# Sitara_Connectors.net
KiCad netlist of a schematic drawn in Altium Designer
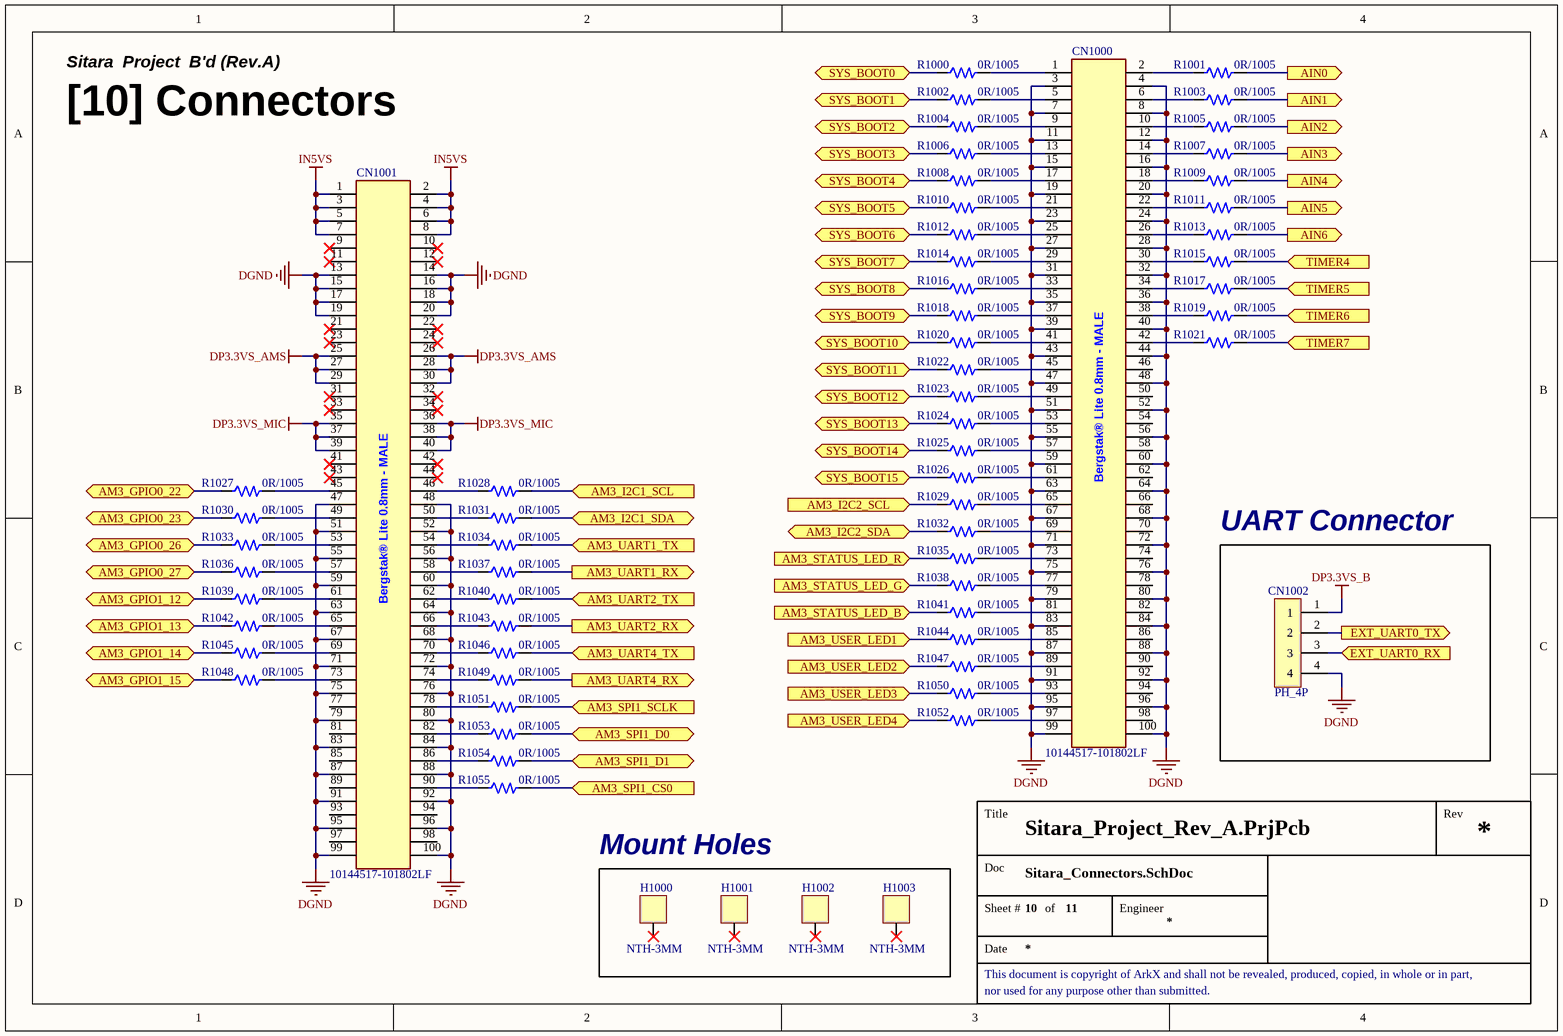
[diagram p0: Sitara_Connectors.SchDoc]

(export (version "E")
  (design (tool "Eeschema 10.0.6"))
  (components
    (comp (ref "CN1000")
      (value "10144517-101802LF")
      (footprint "CON_BergStak-Lite(0.8mm)_MALE-100P(10144517-101802LF)_HandSolder")
      (libsource (lib "Arkx") (part "CON_BergStak-Lite(0.8mm)_MALE-100P(10144517-101802LF)"))
    )
    (comp (ref "CN1001")
      (value "10144517-101802LF")
      (footprint "CON_BergStak-Lite(0.8mm)_MALE-100P(10144517-101802LF)_HandSolder")
      (libsource (lib "Arkx") (part "CON_BergStak-Lite(0.8mm)_MALE-100P(10144517-101802LF)"))
    )
    (comp (ref "CN1002")
      (value "PH_4P")
      (footprint "CON PIN_HEADER-4PIN(2.54MM)")
      (description "CON_PIN_HEADER_SINGLE-4PIN(2.54MM)")
      (libsource (lib "Arkx") (part "CON_PIN_HEADER_SINGLE-4PIN(2.54MM)"))
    )
    (comp (ref "H1000")
      (value "NTH-3MM")
      (footprint "HOLE NTH-3MM")
      (description "Non-Through Hole 3mm")
      (libsource (lib "Arkx") (part "HOLE_NTH-3MM"))
    )
    (comp (ref "H1001")
      (value "NTH-3MM")
      (footprint "HOLE NTH-3MM")
      (description "Non-Through Hole 3mm")
      (libsource (lib "Arkx") (part "HOLE_NTH-3MM"))
    )
    (comp (ref "H1002")
      (value "NTH-3MM")
      (footprint "HOLE NTH-3MM")
      (description "Non-Through Hole 3mm")
      (libsource (lib "Arkx") (part "HOLE_NTH-3MM"))
    )
    (comp (ref "H1003")
      (value "NTH-3MM")
      (footprint "HOLE NTH-3MM")
      (description "Non-Through Hole 3mm")
      (libsource (lib "Arkx") (part "HOLE_NTH-3MM"))
    )
    (comp (ref "R1000")
      (value "0R/1005")
      (footprint "RES 1005 (0402_inch)")
      (description "RES_0R/1005/62.5mW")
      (fields (field (name "LCSC PART #") "C17168"))
      (libsource (lib "Arkx") (part "RES_0R/1005/62.5mW"))
    )
    (comp (ref "R1001")
      (value "0R/1005")
      (footprint "RES 1005 (0402_inch)")
      (description "RES_0R/1005/62.5mW")
      (fields (field (name "LCSC PART #") "C17168"))
      (libsource (lib "Arkx") (part "RES_0R/1005/62.5mW"))
    )
    (comp (ref "R1002")
      (value "0R/1005")
      (footprint "RES 1005 (0402_inch)")
      (description "RES_0R/1005/62.5mW")
      (fields (field (name "LCSC PART #") "C17168"))
      (libsource (lib "Arkx") (part "RES_0R/1005/62.5mW"))
    )
    (comp (ref "R1003")
      (value "0R/1005")
      (footprint "RES 1005 (0402_inch)")
      (description "RES_0R/1005/62.5mW")
      (fields (field (name "LCSC PART #") "C17168"))
      (libsource (lib "Arkx") (part "RES_0R/1005/62.5mW"))
    )
    (comp (ref "R1004")
      (value "0R/1005")
      (footprint "RES 1005 (0402_inch)")
      (description "RES_0R/1005/62.5mW")
      (fields (field (name "LCSC PART #") "C17168"))
      (libsource (lib "Arkx") (part "RES_0R/1005/62.5mW"))
    )
    (comp (ref "R1005")
      (value "0R/1005")
      (footprint "RES 1005 (0402_inch)")
      (description "RES_0R/1005/62.5mW")
      (fields (field (name "LCSC PART #") "C17168"))
      (libsource (lib "Arkx") (part "RES_0R/1005/62.5mW"))
    )
    (comp (ref "R1006")
      (value "0R/1005")
      (footprint "RES 1005 (0402_inch)")
      (description "RES_0R/1005/62.5mW")
      (fields (field (name "LCSC PART #") "C17168"))
      (libsource (lib "Arkx") (part "RES_0R/1005/62.5mW"))
    )
    (comp (ref "R1007")
      (value "0R/1005")
      (footprint "RES 1005 (0402_inch)")
      (description "RES_0R/1005/62.5mW")
      (fields (field (name "LCSC PART #") "C17168"))
      (libsource (lib "Arkx") (part "RES_0R/1005/62.5mW"))
    )
    (comp (ref "R1008")
      (value "0R/1005")
      (footprint "RES 1005 (0402_inch)")
      (description "RES_0R/1005/62.5mW")
      (fields (field (name "LCSC PART #") "C17168"))
      (libsource (lib "Arkx") (part "RES_0R/1005/62.5mW"))
    )
    (comp (ref "R1009")
      (value "0R/1005")
      (footprint "RES 1005 (0402_inch)")
      (description "RES_0R/1005/62.5mW")
      (fields (field (name "LCSC PART #") "C17168"))
      (libsource (lib "Arkx") (part "RES_0R/1005/62.5mW"))
    )
    (comp (ref "R1010")
      (value "0R/1005")
      (footprint "RES 1005 (0402_inch)")
      (description "RES_0R/1005/62.5mW")
      (fields (field (name "LCSC PART #") "C17168"))
      (libsource (lib "Arkx") (part "RES_0R/1005/62.5mW"))
    )
    (comp (ref "R1011")
      (value "0R/1005")
      (footprint "RES 1005 (0402_inch)")
      (description "RES_0R/1005/62.5mW")
      (fields (field (name "LCSC PART #") "C17168"))
      (libsource (lib "Arkx") (part "RES_0R/1005/62.5mW"))
    )
    (comp (ref "R1012")
      (value "0R/1005")
      (footprint "RES 1005 (0402_inch)")
      (description "RES_0R/1005/62.5mW")
      (fields (field (name "LCSC PART #") "C17168"))
      (libsource (lib "Arkx") (part "RES_0R/1005/62.5mW"))
    )
    (comp (ref "R1013")
      (value "0R/1005")
      (footprint "RES 1005 (0402_inch)")
      (description "RES_0R/1005/62.5mW")
      (fields (field (name "LCSC PART #") "C17168"))
      (libsource (lib "Arkx") (part "RES_0R/1005/62.5mW"))
    )
    (comp (ref "R1014")
      (value "0R/1005")
      (footprint "RES 1005 (0402_inch)")
      (description "RES_0R/1005/62.5mW")
      (fields (field (name "LCSC PART #") "C17168"))
      (libsource (lib "Arkx") (part "RES_0R/1005/62.5mW"))
    )
    (comp (ref "R1015")
      (value "0R/1005")
      (footprint "RES 1005 (0402_inch)")
      (description "RES_0R/1005/62.5mW")
      (fields (field (name "LCSC PART #") "C17168"))
      (libsource (lib "Arkx") (part "RES_0R/1005/62.5mW"))
    )
    (comp (ref "R1016")
      (value "0R/1005")
      (footprint "RES 1005 (0402_inch)")
      (description "RES_0R/1005/62.5mW")
      (fields (field (name "LCSC PART #") "C17168"))
      (libsource (lib "Arkx") (part "RES_0R/1005/62.5mW"))
    )
    (comp (ref "R1017")
      (value "0R/1005")
      (footprint "RES 1005 (0402_inch)")
      (description "RES_0R/1005/62.5mW")
      (fields (field (name "LCSC PART #") "C17168"))
      (libsource (lib "Arkx") (part "RES_0R/1005/62.5mW"))
    )
    (comp (ref "R1018")
      (value "0R/1005")
      (footprint "RES 1005 (0402_inch)")
      (description "RES_0R/1005/62.5mW")
      (fields (field (name "LCSC PART #") "C17168"))
      (libsource (lib "Arkx") (part "RES_0R/1005/62.5mW"))
    )
    (comp (ref "R1019")
      (value "0R/1005")
      (footprint "RES 1005 (0402_inch)")
      (description "RES_0R/1005/62.5mW")
      (fields (field (name "LCSC PART #") "C17168"))
      (libsource (lib "Arkx") (part "RES_0R/1005/62.5mW"))
    )
    (comp (ref "R1020")
      (value "0R/1005")
      (footprint "RES 1005 (0402_inch)")
      (description "RES_0R/1005/62.5mW")
      (fields (field (name "LCSC PART #") "C17168"))
      (libsource (lib "Arkx") (part "RES_0R/1005/62.5mW"))
    )
    (comp (ref "R1021")
      (value "0R/1005")
      (footprint "RES 1005 (0402_inch)")
      (description "RES_0R/1005/62.5mW")
      (fields (field (name "LCSC PART #") "C17168"))
      (libsource (lib "Arkx") (part "RES_0R/1005/62.5mW"))
    )
    (comp (ref "R1022")
      (value "0R/1005")
      (footprint "RES 1005 (0402_inch)")
      (description "RES_0R/1005/62.5mW")
      (fields (field (name "LCSC PART #") "C17168"))
      (libsource (lib "Arkx") (part "RES_0R/1005/62.5mW"))
    )
    (comp (ref "R1023")
      (value "0R/1005")
      (footprint "RES 1005 (0402_inch)")
      (description "RES_0R/1005/62.5mW")
      (fields (field (name "LCSC PART #") "C17168"))
      (libsource (lib "Arkx") (part "RES_0R/1005/62.5mW"))
    )
    (comp (ref "R1024")
      (value "0R/1005")
      (footprint "RES 1005 (0402_inch)")
      (description "RES_0R/1005/62.5mW")
      (fields (field (name "LCSC PART #") "C17168"))
      (libsource (lib "Arkx") (part "RES_0R/1005/62.5mW"))
    )
    (comp (ref "R1025")
      (value "0R/1005")
      (footprint "RES 1005 (0402_inch)")
      (description "RES_0R/1005/62.5mW")
      (fields (field (name "LCSC PART #") "C17168"))
      (libsource (lib "Arkx") (part "RES_0R/1005/62.5mW"))
    )
    (comp (ref "R1026")
      (value "0R/1005")
      (footprint "RES 1005 (0402_inch)")
      (description "RES_0R/1005/62.5mW")
      (fields (field (name "LCSC PART #") "C17168"))
      (libsource (lib "Arkx") (part "RES_0R/1005/62.5mW"))
    )
    (comp (ref "R1027")
      (value "0R/1005")
      (footprint "RES 1005 (0402_inch)")
      (description "RES_0R/1005/62.5mW")
      (fields (field (name "LCSC PART #") "C17168"))
      (libsource (lib "Arkx") (part "RES_0R/1005/62.5mW"))
    )
    (comp (ref "R1028")
      (value "0R/1005")
      (footprint "RES 1005 (0402_inch)")
      (description "RES_0R/1005/62.5mW")
      (fields (field (name "LCSC PART #") "C17168"))
      (libsource (lib "Arkx") (part "RES_0R/1005/62.5mW"))
    )
    (comp (ref "R1029")
      (value "0R/1005")
      (footprint "RES 1005 (0402_inch)")
      (description "RES_0R/1005/62.5mW")
      (fields (field (name "LCSC PART #") "C17168"))
      (libsource (lib "Arkx") (part "RES_0R/1005/62.5mW"))
    )
    (comp (ref "R1030")
      (value "0R/1005")
      (footprint "RES 1005 (0402_inch)")
      (description "RES_0R/1005/62.5mW")
      (fields (field (name "LCSC PART #") "C17168"))
      (libsource (lib "Arkx") (part "RES_0R/1005/62.5mW"))
    )
    (comp (ref "R1031")
      (value "0R/1005")
      (footprint "RES 1005 (0402_inch)")
      (description "RES_0R/1005/62.5mW")
      (fields (field (name "LCSC PART #") "C17168"))
      (libsource (lib "Arkx") (part "RES_0R/1005/62.5mW"))
    )
    (comp (ref "R1032")
      (value "0R/1005")
      (footprint "RES 1005 (0402_inch)")
      (description "RES_0R/1005/62.5mW")
      (fields (field (name "LCSC PART #") "C17168"))
      (libsource (lib "Arkx") (part "RES_0R/1005/62.5mW"))
    )
    (comp (ref "R1033")
      (value "0R/1005")
      (footprint "RES 1005 (0402_inch)")
      (description "RES_0R/1005/62.5mW")
      (fields (field (name "LCSC PART #") "C17168"))
      (libsource (lib "Arkx") (part "RES_0R/1005/62.5mW"))
    )
    (comp (ref "R1034")
      (value "0R/1005")
      (footprint "RES 1005 (0402_inch)")
      (description "RES_0R/1005/62.5mW")
      (fields (field (name "LCSC PART #") "C17168"))
      (libsource (lib "Arkx") (part "RES_0R/1005/62.5mW"))
    )
    (comp (ref "R1035")
      (value "0R/1005")
      (footprint "RES 1005 (0402_inch)")
      (description "RES_0R/1005/62.5mW")
      (fields (field (name "LCSC PART #") "C17168"))
      (libsource (lib "Arkx") (part "RES_0R/1005/62.5mW"))
    )
    (comp (ref "R1036")
      (value "0R/1005")
      (footprint "RES 1005 (0402_inch)")
      (description "RES_0R/1005/62.5mW")
      (fields (field (name "LCSC PART #") "C17168"))
      (libsource (lib "Arkx") (part "RES_0R/1005/62.5mW"))
    )
    (comp (ref "R1037")
      (value "0R/1005")
      (footprint "RES 1005 (0402_inch)")
      (description "RES_0R/1005/62.5mW")
      (fields (field (name "LCSC PART #") "C17168"))
      (libsource (lib "Arkx") (part "RES_0R/1005/62.5mW"))
    )
    (comp (ref "R1038")
      (value "0R/1005")
      (footprint "RES 1005 (0402_inch)")
      (description "RES_0R/1005/62.5mW")
      (fields (field (name "LCSC PART #") "C17168"))
      (libsource (lib "Arkx") (part "RES_0R/1005/62.5mW"))
    )
    (comp (ref "R1039")
      (value "0R/1005")
      (footprint "RES 1005 (0402_inch)")
      (description "RES_0R/1005/62.5mW")
      (fields (field (name "LCSC PART #") "C17168"))
      (libsource (lib "Arkx") (part "RES_0R/1005/62.5mW"))
    )
    (comp (ref "R1040")
      (value "0R/1005")
      (footprint "RES 1005 (0402_inch)")
      (description "RES_0R/1005/62.5mW")
      (fields (field (name "LCSC PART #") "C17168"))
      (libsource (lib "Arkx") (part "RES_0R/1005/62.5mW"))
    )
    (comp (ref "R1041")
      (value "0R/1005")
      (footprint "RES 1005 (0402_inch)")
      (description "RES_0R/1005/62.5mW")
      (fields (field (name "LCSC PART #") "C17168"))
      (libsource (lib "Arkx") (part "RES_0R/1005/62.5mW"))
    )
    (comp (ref "R1042")
      (value "0R/1005")
      (footprint "RES 1005 (0402_inch)")
      (description "RES_0R/1005/62.5mW")
      (fields (field (name "LCSC PART #") "C17168"))
      (libsource (lib "Arkx") (part "RES_0R/1005/62.5mW"))
    )
    (comp (ref "R1043")
      (value "0R/1005")
      (footprint "RES 1005 (0402_inch)")
      (description "RES_0R/1005/62.5mW")
      (fields (field (name "LCSC PART #") "C17168"))
      (libsource (lib "Arkx") (part "RES_0R/1005/62.5mW"))
    )
    (comp (ref "R1044")
      (value "0R/1005")
      (footprint "RES 1005 (0402_inch)")
      (description "RES_0R/1005/62.5mW")
      (fields (field (name "LCSC PART #") "C17168"))
      (libsource (lib "Arkx") (part "RES_0R/1005/62.5mW"))
    )
    (comp (ref "R1045")
      (value "0R/1005")
      (footprint "RES 1005 (0402_inch)")
      (description "RES_0R/1005/62.5mW")
      (fields (field (name "LCSC PART #") "C17168"))
      (libsource (lib "Arkx") (part "RES_0R/1005/62.5mW"))
    )
    (comp (ref "R1046")
      (value "0R/1005")
      (footprint "RES 1005 (0402_inch)")
      (description "RES_0R/1005/62.5mW")
      (fields (field (name "LCSC PART #") "C17168"))
      (libsource (lib "Arkx") (part "RES_0R/1005/62.5mW"))
    )
    (comp (ref "R1047")
      (value "0R/1005")
      (footprint "RES 1005 (0402_inch)")
      (description "RES_0R/1005/62.5mW")
      (fields (field (name "LCSC PART #") "C17168"))
      (libsource (lib "Arkx") (part "RES_0R/1005/62.5mW"))
    )
    (comp (ref "R1048")
      (value "0R/1005")
      (footprint "RES 1005 (0402_inch)")
      (description "RES_0R/1005/62.5mW")
      (fields (field (name "LCSC PART #") "C17168"))
      (libsource (lib "Arkx") (part "RES_0R/1005/62.5mW"))
    )
    (comp (ref "R1049")
      (value "0R/1005")
      (footprint "RES 1005 (0402_inch)")
      (description "RES_0R/1005/62.5mW")
      (fields (field (name "LCSC PART #") "C17168"))
      (libsource (lib "Arkx") (part "RES_0R/1005/62.5mW"))
    )
    (comp (ref "R1050")
      (value "0R/1005")
      (footprint "RES 1005 (0402_inch)")
      (description "RES_0R/1005/62.5mW")
      (fields (field (name "LCSC PART #") "C17168"))
      (libsource (lib "Arkx") (part "RES_0R/1005/62.5mW"))
    )
    (comp (ref "R1051")
      (value "0R/1005")
      (footprint "RES 1005 (0402_inch)")
      (description "RES_0R/1005/62.5mW")
      (fields (field (name "LCSC PART #") "C17168"))
      (libsource (lib "Arkx") (part "RES_0R/1005/62.5mW"))
    )
    (comp (ref "R1052")
      (value "0R/1005")
      (footprint "RES 1005 (0402_inch)")
      (description "RES_0R/1005/62.5mW")
      (fields (field (name "LCSC PART #") "C17168"))
      (libsource (lib "Arkx") (part "RES_0R/1005/62.5mW"))
    )
    (comp (ref "R1053")
      (value "0R/1005")
      (footprint "RES 1005 (0402_inch)")
      (description "RES_0R/1005/62.5mW")
      (fields (field (name "LCSC PART #") "C17168"))
      (libsource (lib "Arkx") (part "RES_0R/1005/62.5mW"))
    )
    (comp (ref "R1054")
      (value "0R/1005")
      (footprint "RES 1005 (0402_inch)")
      (description "RES_0R/1005/62.5mW")
      (fields (field (name "LCSC PART #") "C17168"))
      (libsource (lib "Arkx") (part "RES_0R/1005/62.5mW"))
    )
    (comp (ref "R1055")
      (value "0R/1005")
      (footprint "RES 1005 (0402_inch)")
      (description "RES_0R/1005/62.5mW")
      (fields (field (name "LCSC PART #") "C17168"))
      (libsource (lib "Arkx") (part "RES_0R/1005/62.5mW"))
    )
  )
  (nets
    (net (code "1") (name "/AIN0") (class "Default")
      (node (ref "R1001") (pin "2") (pinfunction "2_2") (pintype "passive"))
    )
    (net (code "2") (name "/AIN1") (class "Default")
      (node (ref "R1003") (pin "2") (pinfunction "2_2") (pintype "passive"))
    )
    (net (code "3") (name "/AIN2") (class "Default")
      (node (ref "R1005") (pin "2") (pinfunction "2_2") (pintype "passive"))
    )
    (net (code "4") (name "/AIN3") (class "Default")
      (node (ref "R1007") (pin "2") (pinfunction "2_2") (pintype "passive"))
    )
    (net (code "5") (name "/AIN4") (class "Default")
      (node (ref "R1009") (pin "2") (pinfunction "2_2") (pintype "passive"))
    )
    (net (code "6") (name "/AIN5") (class "Default")
      (node (ref "R1011") (pin "2") (pinfunction "2_2") (pintype "passive"))
    )
    (net (code "7") (name "/AIN6") (class "Default")
      (node (ref "R1013") (pin "2") (pinfunction "2_2") (pintype "passive"))
    )
    (net (code "8") (name "/AM3_GPIO0_22") (class "Default")
      (node (ref "R1027") (pin "1") (pinfunction "1_1") (pintype "passive"))
    )
    (net (code "9") (name "/AM3_GPIO0_23") (class "Default")
      (node (ref "R1030") (pin "1") (pinfunction "1_1") (pintype "passive"))
    )
    (net (code "10") (name "/AM3_GPIO0_26") (class "Default")
      (node (ref "R1033") (pin "1") (pinfunction "1_1") (pintype "passive"))
    )
    (net (code "11") (name "/AM3_GPIO0_27") (class "Default")
      (node (ref "R1036") (pin "1") (pinfunction "1_1") (pintype "passive"))
    )
    (net (code "12") (name "/AM3_GPIO1_12") (class "Default")
      (node (ref "R1039") (pin "1") (pinfunction "1_1") (pintype "passive"))
    )
    (net (code "13") (name "/AM3_GPIO1_13") (class "Default")
      (node (ref "R1042") (pin "1") (pinfunction "1_1") (pintype "passive"))
    )
    (net (code "14") (name "/AM3_GPIO1_14") (class "Default")
      (node (ref "R1045") (pin "1") (pinfunction "1_1") (pintype "passive"))
    )
    (net (code "15") (name "/AM3_GPIO1_15") (class "Default")
      (node (ref "R1048") (pin "1") (pinfunction "1_1") (pintype "passive"))
    )
    (net (code "16") (name "/AM3_I2C1_SCL") (class "Default")
      (node (ref "R1028") (pin "2") (pinfunction "2_2") (pintype "passive"))
    )
    (net (code "17") (name "/AM3_I2C1_SDA") (class "Default")
      (node (ref "R1031") (pin "2") (pinfunction "2_2") (pintype "passive"))
    )
    (net (code "18") (name "/AM3_I2C2_SCL") (class "Default")
      (node (ref "R1029") (pin "1") (pinfunction "1_1") (pintype "passive"))
    )
    (net (code "19") (name "/AM3_I2C2_SDA") (class "Default")
      (node (ref "R1032") (pin "1") (pinfunction "1_1") (pintype "passive"))
    )
    (net (code "20") (name "/AM3_SPI1_CS0") (class "Default")
      (node (ref "R1055") (pin "2") (pinfunction "2_2") (pintype "passive"))
    )
    (net (code "21") (name "/AM3_SPI1_D0") (class "Default")
      (node (ref "R1053") (pin "2") (pinfunction "2_2") (pintype "passive"))
    )
    (net (code "22") (name "/AM3_SPI1_D1") (class "Default")
      (node (ref "R1054") (pin "2") (pinfunction "2_2") (pintype "passive"))
    )
    (net (code "23") (name "/AM3_SPI1_SCLK") (class "Default")
      (node (ref "R1051") (pin "2") (pinfunction "2_2") (pintype "passive"))
    )
    (net (code "24") (name "/AM3_STATUS_LED_B") (class "Default")
      (node (ref "R1041") (pin "1") (pinfunction "1_1") (pintype "passive"))
    )
    (net (code "25") (name "/AM3_STATUS_LED_G") (class "Default")
      (node (ref "R1038") (pin "1") (pinfunction "1_1") (pintype "passive"))
    )
    (net (code "26") (name "/AM3_STATUS_LED_R") (class "Default")
      (node (ref "R1035") (pin "1") (pinfunction "1_1") (pintype "passive"))
    )
    (net (code "27") (name "/AM3_UART1_RX") (class "Default")
      (node (ref "R1037") (pin "2") (pinfunction "2_2") (pintype "passive"))
    )
    (net (code "28") (name "/AM3_UART1_TX") (class "Default")
      (node (ref "R1034") (pin "2") (pinfunction "2_2") (pintype "passive"))
    )
    (net (code "29") (name "/AM3_UART2_RX") (class "Default")
      (node (ref "R1043") (pin "2") (pinfunction "2_2") (pintype "passive"))
    )
    (net (code "30") (name "/AM3_UART2_TX") (class "Default")
      (node (ref "R1040") (pin "2") (pinfunction "2_2") (pintype "passive"))
    )
    (net (code "31") (name "/AM3_UART4_RX") (class "Default")
      (node (ref "R1049") (pin "2") (pinfunction "2_2") (pintype "passive"))
    )
    (net (code "32") (name "/AM3_UART4_TX") (class "Default")
      (node (ref "R1046") (pin "2") (pinfunction "2_2") (pintype "passive"))
    )
    (net (code "33") (name "/AM3_USER_LED1") (class "Default")
      (node (ref "R1044") (pin "1") (pinfunction "1_1") (pintype "passive"))
    )
    (net (code "34") (name "/AM3_USER_LED2") (class "Default")
      (node (ref "R1047") (pin "1") (pinfunction "1_1") (pintype "passive"))
    )
    (net (code "35") (name "/AM3_USER_LED3") (class "Default")
      (node (ref "R1050") (pin "1") (pinfunction "1_1") (pintype "passive"))
    )
    (net (code "36") (name "/AM3_USER_LED4") (class "Default")
      (node (ref "R1052") (pin "1") (pinfunction "1_1") (pintype "passive"))
    )
    (net (code "37") (name "/EXT_UART0_RX") (class "Default")
      (node (ref "CN1002") (pin "3") (pinfunction "3_3") (pintype "passive"))
    )
    (net (code "38") (name "/EXT_UART0_TX") (class "Default")
      (node (ref "CN1002") (pin "2") (pinfunction "2_2") (pintype "passive"))
    )
    (net (code "39") (name "/SYS_BOOT0") (class "Default")
      (node (ref "R1000") (pin "1") (pinfunction "1_1") (pintype "passive"))
    )
    (net (code "40") (name "/SYS_BOOT1") (class "Default")
      (node (ref "R1002") (pin "1") (pinfunction "1_1") (pintype "passive"))
    )
    (net (code "41") (name "/SYS_BOOT2") (class "Default")
      (node (ref "R1004") (pin "1") (pinfunction "1_1") (pintype "passive"))
    )
    (net (code "42") (name "/SYS_BOOT3") (class "Default")
      (node (ref "R1006") (pin "1") (pinfunction "1_1") (pintype "passive"))
    )
    (net (code "43") (name "/SYS_BOOT4") (class "Default")
      (node (ref "R1008") (pin "1") (pinfunction "1_1") (pintype "passive"))
    )
    (net (code "44") (name "/SYS_BOOT5") (class "Default")
      (node (ref "R1010") (pin "1") (pinfunction "1_1") (pintype "passive"))
    )
    (net (code "45") (name "/SYS_BOOT6") (class "Default")
      (node (ref "R1012") (pin "1") (pinfunction "1_1") (pintype "passive"))
    )
    (net (code "46") (name "/SYS_BOOT7") (class "Default")
      (node (ref "R1014") (pin "1") (pinfunction "1_1") (pintype "passive"))
    )
    (net (code "47") (name "/SYS_BOOT8") (class "Default")
      (node (ref "R1016") (pin "1") (pinfunction "1_1") (pintype "passive"))
    )
    (net (code "48") (name "/SYS_BOOT9") (class "Default")
      (node (ref "R1018") (pin "1") (pinfunction "1_1") (pintype "passive"))
    )
    (net (code "49") (name "/SYS_BOOT10") (class "Default")
      (node (ref "R1020") (pin "1") (pinfunction "1_1") (pintype "passive"))
    )
    (net (code "50") (name "/SYS_BOOT11") (class "Default")
      (node (ref "R1022") (pin "1") (pinfunction "1_1") (pintype "passive"))
    )
    (net (code "51") (name "/SYS_BOOT12") (class "Default")
      (node (ref "R1023") (pin "1") (pinfunction "1_1") (pintype "passive"))
    )
    (net (code "52") (name "/SYS_BOOT13") (class "Default")
      (node (ref "R1024") (pin "1") (pinfunction "1_1") (pintype "passive"))
    )
    (net (code "53") (name "/SYS_BOOT14") (class "Default")
      (node (ref "R1025") (pin "1") (pinfunction "1_1") (pintype "passive"))
    )
    (net (code "54") (name "/SYS_BOOT15") (class "Default")
      (node (ref "R1026") (pin "1") (pinfunction "1_1") (pintype "passive"))
    )
    (net (code "55") (name "/TIMER4") (class "Default")
      (node (ref "R1015") (pin "2") (pinfunction "2_2") (pintype "passive"))
    )
    (net (code "56") (name "/TIMER5") (class "Default")
      (node (ref "R1017") (pin "2") (pinfunction "2_2") (pintype "passive"))
    )
    (net (code "57") (name "/TIMER6") (class "Default")
      (node (ref "R1019") (pin "2") (pinfunction "2_2") (pintype "passive"))
    )
    (net (code "58") (name "/TIMER7") (class "Default")
      (node (ref "R1021") (pin "2") (pinfunction "2_2") (pintype "passive"))
    )
    (net (code "59") (name "DGND") (class "Default")
      (node (ref "CN1000") (pin "100") (pinfunction "100_100") (pintype "passive"))
      (node (ref "CN1000") (pin "11") (pinfunction "11_11") (pintype "passive"))
      (node (ref "CN1000") (pin "12") (pinfunction "12_12") (pintype "passive"))
      (node (ref "CN1000") (pin "15") (pinfunction "15_15") (pintype "passive"))
      (node (ref "CN1000") (pin "16") (pinfunction "16_16") (pintype "passive"))
      (node (ref "CN1000") (pin "19") (pinfunction "19_19") (pintype "passive"))
      (node (ref "CN1000") (pin "20") (pinfunction "20_20") (pintype "passive"))
      (node (ref "CN1000") (pin "23") (pinfunction "23_23") (pintype "passive"))
      (node (ref "CN1000") (pin "24") (pinfunction "24_24") (pintype "passive"))
      (node (ref "CN1000") (pin "27") (pinfunction "27_27") (pintype "passive"))
      (node (ref "CN1000") (pin "28") (pinfunction "28_28") (pintype "passive"))
      (node (ref "CN1000") (pin "3") (pinfunction "3_3") (pintype "passive"))
      (node (ref "CN1000") (pin "31") (pinfunction "31_31") (pintype "passive"))
      (node (ref "CN1000") (pin "32") (pinfunction "32_32") (pintype "passive"))
      (node (ref "CN1000") (pin "35") (pinfunction "35_35") (pintype "passive"))
      (node (ref "CN1000") (pin "36") (pinfunction "36_36") (pintype "passive"))
      (node (ref "CN1000") (pin "39") (pinfunction "39_39") (pintype "passive"))
      (node (ref "CN1000") (pin "4") (pinfunction "4_4") (pintype "passive"))
      (node (ref "CN1000") (pin "40") (pinfunction "40_40") (pintype "passive"))
      (node (ref "CN1000") (pin "43") (pinfunction "43_43") (pintype "passive"))
      (node (ref "CN1000") (pin "44") (pinfunction "44_44") (pintype "passive"))
      (node (ref "CN1000") (pin "47") (pinfunction "47_47") (pintype "passive"))
      (node (ref "CN1000") (pin "48") (pinfunction "48_48") (pintype "passive"))
      (node (ref "CN1000") (pin "51") (pinfunction "51_51") (pintype "passive"))
      (node (ref "CN1000") (pin "52") (pinfunction "52_52") (pintype "passive"))
      (node (ref "CN1000") (pin "55") (pinfunction "55_55") (pintype "passive"))
      (node (ref "CN1000") (pin "56") (pinfunction "56_56") (pintype "passive"))
      (node (ref "CN1000") (pin "59") (pinfunction "59_59") (pintype "passive"))
      (node (ref "CN1000") (pin "60") (pinfunction "60_60") (pintype "passive"))
      (node (ref "CN1000") (pin "63") (pinfunction "63_63") (pintype "passive"))
      (node (ref "CN1000") (pin "64") (pinfunction "64_64") (pintype "passive"))
      (node (ref "CN1000") (pin "67") (pinfunction "67_67") (pintype "passive"))
      (node (ref "CN1000") (pin "68") (pinfunction "68_68") (pintype "passive"))
      (node (ref "CN1000") (pin "7") (pinfunction "7_7") (pintype "passive"))
      (node (ref "CN1000") (pin "71") (pinfunction "71_71") (pintype "passive"))
      (node (ref "CN1000") (pin "72") (pinfunction "72_72") (pintype "passive"))
      (node (ref "CN1000") (pin "75") (pinfunction "75_75") (pintype "passive"))
      (node (ref "CN1000") (pin "76") (pinfunction "76_76") (pintype "passive"))
      (node (ref "CN1000") (pin "79") (pinfunction "79_79") (pintype "passive"))
      (node (ref "CN1000") (pin "8") (pinfunction "8_8") (pintype "passive"))
      (node (ref "CN1000") (pin "80") (pinfunction "80_80") (pintype "passive"))
      (node (ref "CN1000") (pin "83") (pinfunction "83_83") (pintype "passive"))
      (node (ref "CN1000") (pin "84") (pinfunction "84_84") (pintype "passive"))
      (node (ref "CN1000") (pin "87") (pinfunction "87_87") (pintype "passive"))
      (node (ref "CN1000") (pin "88") (pinfunction "88_88") (pintype "passive"))
      (node (ref "CN1000") (pin "91") (pinfunction "91_91") (pintype "passive"))
      (node (ref "CN1000") (pin "92") (pinfunction "92_92") (pintype "passive"))
      (node (ref "CN1000") (pin "95") (pinfunction "95_95") (pintype "passive"))
      (node (ref "CN1000") (pin "96") (pinfunction "96_96") (pintype "passive"))
      (node (ref "CN1000") (pin "99") (pinfunction "99_99") (pintype "passive"))
      (node (ref "CN1001") (pin "100") (pinfunction "100_100") (pintype "passive"))
      (node (ref "CN1001") (pin "13") (pinfunction "13_13") (pintype "passive"))
      (node (ref "CN1001") (pin "14") (pinfunction "14_14") (pintype "passive"))
      (node (ref "CN1001") (pin "15") (pinfunction "15_15") (pintype "passive"))
      (node (ref "CN1001") (pin "16") (pinfunction "16_16") (pintype "passive"))
      (node (ref "CN1001") (pin "17") (pinfunction "17_17") (pintype "passive"))
      (node (ref "CN1001") (pin "18") (pinfunction "18_18") (pintype "passive"))
      (node (ref "CN1001") (pin "19") (pinfunction "19_19") (pintype "passive"))
      (node (ref "CN1001") (pin "20") (pinfunction "20_20") (pintype "passive"))
      (node (ref "CN1001") (pin "47") (pinfunction "47_47") (pintype "passive"))
      (node (ref "CN1001") (pin "48") (pinfunction "48_48") (pintype "passive"))
      (node (ref "CN1001") (pin "51") (pinfunction "51_51") (pintype "passive"))
      (node (ref "CN1001") (pin "52") (pinfunction "52_52") (pintype "passive"))
      (node (ref "CN1001") (pin "55") (pinfunction "55_55") (pintype "passive"))
      (node (ref "CN1001") (pin "56") (pinfunction "56_56") (pintype "passive"))
      (node (ref "CN1001") (pin "59") (pinfunction "59_59") (pintype "passive"))
      (node (ref "CN1001") (pin "60") (pinfunction "60_60") (pintype "passive"))
      (node (ref "CN1001") (pin "63") (pinfunction "63_63") (pintype "passive"))
      (node (ref "CN1001") (pin "64") (pinfunction "64_64") (pintype "passive"))
      (node (ref "CN1001") (pin "67") (pinfunction "67_67") (pintype "passive"))
      (node (ref "CN1001") (pin "68") (pinfunction "68_68") (pintype "passive"))
      (node (ref "CN1001") (pin "71") (pinfunction "71_71") (pintype "passive"))
      (node (ref "CN1001") (pin "72") (pinfunction "72_72") (pintype "passive"))
      (node (ref "CN1001") (pin "75") (pinfunction "75_75") (pintype "passive"))
      (node (ref "CN1001") (pin "76") (pinfunction "76_76") (pintype "passive"))
      (node (ref "CN1001") (pin "79") (pinfunction "79_79") (pintype "passive"))
      (node (ref "CN1001") (pin "80") (pinfunction "80_80") (pintype "passive"))
      (node (ref "CN1001") (pin "83") (pinfunction "83_83") (pintype "passive"))
      (node (ref "CN1001") (pin "84") (pinfunction "84_84") (pintype "passive"))
      (node (ref "CN1001") (pin "87") (pinfunction "87_87") (pintype "passive"))
      (node (ref "CN1001") (pin "88") (pinfunction "88_88") (pintype "passive"))
      (node (ref "CN1001") (pin "91") (pinfunction "91_91") (pintype "passive"))
      (node (ref "CN1001") (pin "92") (pinfunction "92_92") (pintype "passive"))
      (node (ref "CN1001") (pin "95") (pinfunction "95_95") (pintype "passive"))
      (node (ref "CN1001") (pin "96") (pinfunction "96_96") (pintype "passive"))
      (node (ref "CN1001") (pin "99") (pinfunction "99_99") (pintype "passive"))
      (node (ref "CN1002") (pin "4") (pinfunction "4_4") (pintype "passive"))
    )
    (net (code "60") (name "DP3.3VS_AMS") (class "Default")
      (node (ref "CN1001") (pin "25") (pinfunction "25_25") (pintype "passive"))
      (node (ref "CN1001") (pin "26") (pinfunction "26_26") (pintype "passive"))
      (node (ref "CN1001") (pin "27") (pinfunction "27_27") (pintype "passive"))
      (node (ref "CN1001") (pin "28") (pinfunction "28_28") (pintype "passive"))
      (node (ref "CN1001") (pin "29") (pinfunction "29_29") (pintype "passive"))
      (node (ref "CN1001") (pin "30") (pinfunction "30_30") (pintype "passive"))
    )
    (net (code "61") (name "DP3.3VS_B") (class "Default")
      (node (ref "CN1002") (pin "1") (pinfunction "1_1") (pintype "passive"))
    )
    (net (code "62") (name "DP3.3VS_MIC") (class "Default")
      (node (ref "CN1001") (pin "35") (pinfunction "35_35") (pintype "passive"))
      (node (ref "CN1001") (pin "36") (pinfunction "36_36") (pintype "passive"))
      (node (ref "CN1001") (pin "37") (pinfunction "37_37") (pintype "passive"))
      (node (ref "CN1001") (pin "38") (pinfunction "38_38") (pintype "passive"))
      (node (ref "CN1001") (pin "39") (pinfunction "39_39") (pintype "passive"))
      (node (ref "CN1001") (pin "40") (pinfunction "40_40") (pintype "passive"))
    )
    (net (code "63") (name "IN5VS") (class "Default")
      (node (ref "CN1001") (pin "1") (pinfunction "1_1") (pintype "passive"))
      (node (ref "CN1001") (pin "2") (pinfunction "2_2") (pintype "passive"))
      (node (ref "CN1001") (pin "3") (pinfunction "3_3") (pintype "passive"))
      (node (ref "CN1001") (pin "4") (pinfunction "4_4") (pintype "passive"))
      (node (ref "CN1001") (pin "5") (pinfunction "5_5") (pintype "passive"))
      (node (ref "CN1001") (pin "6") (pinfunction "6_6") (pintype "passive"))
      (node (ref "CN1001") (pin "7") (pinfunction "7_7") (pintype "passive"))
      (node (ref "CN1001") (pin "8") (pinfunction "8_8") (pintype "passive"))
    )
    (net (code "64") (name "Net-(CN1000-Pad1)") (class "Default")
      (node (ref "CN1000") (pin "1") (pinfunction "1_1") (pintype "passive"))
      (node (ref "R1000") (pin "2") (pinfunction "2_2") (pintype "passive"))
    )
    (net (code "65") (name "Net-(CN1000-Pad2)") (class "Default")
      (node (ref "CN1000") (pin "2") (pinfunction "2_2") (pintype "passive"))
      (node (ref "R1001") (pin "1") (pinfunction "1_1") (pintype "passive"))
    )
    (net (code "66") (name "Net-(CN1000-Pad5)") (class "Default")
      (node (ref "CN1000") (pin "5") (pinfunction "5_5") (pintype "passive"))
      (node (ref "R1002") (pin "2") (pinfunction "2_2") (pintype "passive"))
    )
    (net (code "67") (name "Net-(CN1000-Pad6)") (class "Default")
      (node (ref "CN1000") (pin "6") (pinfunction "6_6") (pintype "passive"))
      (node (ref "R1003") (pin "1") (pinfunction "1_1") (pintype "passive"))
    )
    (net (code "68") (name "Net-(CN1000-Pad9)") (class "Default")
      (node (ref "CN1000") (pin "9") (pinfunction "9_9") (pintype "passive"))
      (node (ref "R1004") (pin "2") (pinfunction "2_2") (pintype "passive"))
    )
    (net (code "69") (name "Net-(CN1000-Pad10)") (class "Default")
      (node (ref "CN1000") (pin "10") (pinfunction "10_10") (pintype "passive"))
      (node (ref "R1005") (pin "1") (pinfunction "1_1") (pintype "passive"))
    )
    (net (code "70") (name "Net-(CN1000-Pad13)") (class "Default")
      (node (ref "CN1000") (pin "13") (pinfunction "13_13") (pintype "passive"))
      (node (ref "R1006") (pin "2") (pinfunction "2_2") (pintype "passive"))
    )
    (net (code "71") (name "Net-(CN1000-Pad14)") (class "Default")
      (node (ref "CN1000") (pin "14") (pinfunction "14_14") (pintype "passive"))
      (node (ref "R1007") (pin "1") (pinfunction "1_1") (pintype "passive"))
    )
    (net (code "72") (name "Net-(CN1000-Pad17)") (class "Default")
      (node (ref "CN1000") (pin "17") (pinfunction "17_17") (pintype "passive"))
      (node (ref "R1008") (pin "2") (pinfunction "2_2") (pintype "passive"))
    )
    (net (code "73") (name "Net-(CN1000-Pad18)") (class "Default")
      (node (ref "CN1000") (pin "18") (pinfunction "18_18") (pintype "passive"))
      (node (ref "R1009") (pin "1") (pinfunction "1_1") (pintype "passive"))
    )
    (net (code "74") (name "Net-(CN1000-Pad21)") (class "Default")
      (node (ref "CN1000") (pin "21") (pinfunction "21_21") (pintype "passive"))
      (node (ref "R1010") (pin "2") (pinfunction "2_2") (pintype "passive"))
    )
    (net (code "75") (name "Net-(CN1000-Pad22)") (class "Default")
      (node (ref "CN1000") (pin "22") (pinfunction "22_22") (pintype "passive"))
      (node (ref "R1011") (pin "1") (pinfunction "1_1") (pintype "passive"))
    )
    (net (code "76") (name "Net-(CN1000-Pad25)") (class "Default")
      (node (ref "CN1000") (pin "25") (pinfunction "25_25") (pintype "passive"))
      (node (ref "R1012") (pin "2") (pinfunction "2_2") (pintype "passive"))
    )
    (net (code "77") (name "Net-(CN1000-Pad26)") (class "Default")
      (node (ref "CN1000") (pin "26") (pinfunction "26_26") (pintype "passive"))
      (node (ref "R1013") (pin "1") (pinfunction "1_1") (pintype "passive"))
    )
    (net (code "78") (name "Net-(CN1000-Pad29)") (class "Default")
      (node (ref "CN1000") (pin "29") (pinfunction "29_29") (pintype "passive"))
      (node (ref "R1014") (pin "2") (pinfunction "2_2") (pintype "passive"))
    )
    (net (code "79") (name "Net-(CN1000-Pad30)") (class "Default")
      (node (ref "CN1000") (pin "30") (pinfunction "30_30") (pintype "passive"))
      (node (ref "R1015") (pin "1") (pinfunction "1_1") (pintype "passive"))
    )
    (net (code "80") (name "Net-(CN1000-Pad33)") (class "Default")
      (node (ref "CN1000") (pin "33") (pinfunction "33_33") (pintype "passive"))
      (node (ref "R1016") (pin "2") (pinfunction "2_2") (pintype "passive"))
    )
    (net (code "81") (name "Net-(CN1000-Pad34)") (class "Default")
      (node (ref "CN1000") (pin "34") (pinfunction "34_34") (pintype "passive"))
      (node (ref "R1017") (pin "1") (pinfunction "1_1") (pintype "passive"))
    )
    (net (code "82") (name "Net-(CN1000-Pad37)") (class "Default")
      (node (ref "CN1000") (pin "37") (pinfunction "37_37") (pintype "passive"))
      (node (ref "R1018") (pin "2") (pinfunction "2_2") (pintype "passive"))
    )
    (net (code "83") (name "Net-(CN1000-Pad38)") (class "Default")
      (node (ref "CN1000") (pin "38") (pinfunction "38_38") (pintype "passive"))
      (node (ref "R1019") (pin "1") (pinfunction "1_1") (pintype "passive"))
    )
    (net (code "84") (name "Net-(CN1000-Pad41)") (class "Default")
      (node (ref "CN1000") (pin "41") (pinfunction "41_41") (pintype "passive"))
      (node (ref "R1020") (pin "2") (pinfunction "2_2") (pintype "passive"))
    )
    (net (code "85") (name "Net-(CN1000-Pad42)") (class "Default")
      (node (ref "CN1000") (pin "42") (pinfunction "42_42") (pintype "passive"))
      (node (ref "R1021") (pin "1") (pinfunction "1_1") (pintype "passive"))
    )
    (net (code "86") (name "Net-(CN1000-Pad45)") (class "Default")
      (node (ref "CN1000") (pin "45") (pinfunction "45_45") (pintype "passive"))
      (node (ref "R1022") (pin "2") (pinfunction "2_2") (pintype "passive"))
    )
    (net (code "87") (name "Net-(CN1000-Pad49)") (class "Default")
      (node (ref "CN1000") (pin "49") (pinfunction "49_49") (pintype "passive"))
      (node (ref "R1023") (pin "2") (pinfunction "2_2") (pintype "passive"))
    )
    (net (code "88") (name "Net-(CN1000-Pad53)") (class "Default")
      (node (ref "CN1000") (pin "53") (pinfunction "53_53") (pintype "passive"))
      (node (ref "R1024") (pin "2") (pinfunction "2_2") (pintype "passive"))
    )
    (net (code "89") (name "Net-(CN1000-Pad57)") (class "Default")
      (node (ref "CN1000") (pin "57") (pinfunction "57_57") (pintype "passive"))
      (node (ref "R1025") (pin "2") (pinfunction "2_2") (pintype "passive"))
    )
    (net (code "90") (name "Net-(CN1000-Pad61)") (class "Default")
      (node (ref "CN1000") (pin "61") (pinfunction "61_61") (pintype "passive"))
      (node (ref "R1026") (pin "2") (pinfunction "2_2") (pintype "passive"))
    )
    (net (code "91") (name "Net-(CN1000-Pad65)") (class "Default")
      (node (ref "CN1000") (pin "65") (pinfunction "65_65") (pintype "passive"))
      (node (ref "R1029") (pin "2") (pinfunction "2_2") (pintype "passive"))
    )
    (net (code "92") (name "Net-(CN1000-Pad69)") (class "Default")
      (node (ref "CN1000") (pin "69") (pinfunction "69_69") (pintype "passive"))
      (node (ref "R1032") (pin "2") (pinfunction "2_2") (pintype "passive"))
    )
    (net (code "93") (name "Net-(CN1000-Pad73)") (class "Default")
      (node (ref "CN1000") (pin "73") (pinfunction "73_73") (pintype "passive"))
      (node (ref "R1035") (pin "2") (pinfunction "2_2") (pintype "passive"))
    )
    (net (code "94") (name "Net-(CN1000-Pad77)") (class "Default")
      (node (ref "CN1000") (pin "77") (pinfunction "77_77") (pintype "passive"))
      (node (ref "R1038") (pin "2") (pinfunction "2_2") (pintype "passive"))
    )
    (net (code "95") (name "Net-(CN1000-Pad81)") (class "Default")
      (node (ref "CN1000") (pin "81") (pinfunction "81_81") (pintype "passive"))
      (node (ref "R1041") (pin "2") (pinfunction "2_2") (pintype "passive"))
    )
    (net (code "96") (name "Net-(CN1000-Pad85)") (class "Default")
      (node (ref "CN1000") (pin "85") (pinfunction "85_85") (pintype "passive"))
      (node (ref "R1044") (pin "2") (pinfunction "2_2") (pintype "passive"))
    )
    (net (code "97") (name "Net-(CN1000-Pad89)") (class "Default")
      (node (ref "CN1000") (pin "89") (pinfunction "89_89") (pintype "passive"))
      (node (ref "R1047") (pin "2") (pinfunction "2_2") (pintype "passive"))
    )
    (net (code "98") (name "Net-(CN1000-Pad93)") (class "Default")
      (node (ref "CN1000") (pin "93") (pinfunction "93_93") (pintype "passive"))
      (node (ref "R1050") (pin "2") (pinfunction "2_2") (pintype "passive"))
    )
    (net (code "99") (name "Net-(CN1000-Pad97)") (class "Default")
      (node (ref "CN1000") (pin "97") (pinfunction "97_97") (pintype "passive"))
      (node (ref "R1052") (pin "2") (pinfunction "2_2") (pintype "passive"))
    )
    (net (code "100") (name "Net-(CN1001-Pad45)") (class "Default")
      (node (ref "CN1001") (pin "45") (pinfunction "45_45") (pintype "passive"))
      (node (ref "R1027") (pin "2") (pinfunction "2_2") (pintype "passive"))
    )
    (net (code "101") (name "Net-(CN1001-Pad46)") (class "Default")
      (node (ref "CN1001") (pin "46") (pinfunction "46_46") (pintype "passive"))
      (node (ref "R1028") (pin "1") (pinfunction "1_1") (pintype "passive"))
    )
    (net (code "102") (name "Net-(CN1001-Pad49)") (class "Default")
      (node (ref "CN1001") (pin "49") (pinfunction "49_49") (pintype "passive"))
      (node (ref "R1030") (pin "2") (pinfunction "2_2") (pintype "passive"))
    )
    (net (code "103") (name "Net-(CN1001-Pad50)") (class "Default")
      (node (ref "CN1001") (pin "50") (pinfunction "50_50") (pintype "passive"))
      (node (ref "R1031") (pin "1") (pinfunction "1_1") (pintype "passive"))
    )
    (net (code "104") (name "Net-(CN1001-Pad53)") (class "Default")
      (node (ref "CN1001") (pin "53") (pinfunction "53_53") (pintype "passive"))
      (node (ref "R1033") (pin "2") (pinfunction "2_2") (pintype "passive"))
    )
    (net (code "105") (name "Net-(CN1001-Pad54)") (class "Default")
      (node (ref "CN1001") (pin "54") (pinfunction "54_54") (pintype "passive"))
      (node (ref "R1034") (pin "1") (pinfunction "1_1") (pintype "passive"))
    )
    (net (code "106") (name "Net-(CN1001-Pad57)") (class "Default")
      (node (ref "CN1001") (pin "57") (pinfunction "57_57") (pintype "passive"))
      (node (ref "R1036") (pin "2") (pinfunction "2_2") (pintype "passive"))
    )
    (net (code "107") (name "Net-(CN1001-Pad58)") (class "Default")
      (node (ref "CN1001") (pin "58") (pinfunction "58_58") (pintype "passive"))
      (node (ref "R1037") (pin "1") (pinfunction "1_1") (pintype "passive"))
    )
    (net (code "108") (name "Net-(CN1001-Pad61)") (class "Default")
      (node (ref "CN1001") (pin "61") (pinfunction "61_61") (pintype "passive"))
      (node (ref "R1039") (pin "2") (pinfunction "2_2") (pintype "passive"))
    )
    (net (code "109") (name "Net-(CN1001-Pad62)") (class "Default")
      (node (ref "CN1001") (pin "62") (pinfunction "62_62") (pintype "passive"))
      (node (ref "R1040") (pin "1") (pinfunction "1_1") (pintype "passive"))
    )
    (net (code "110") (name "Net-(CN1001-Pad65)") (class "Default")
      (node (ref "CN1001") (pin "65") (pinfunction "65_65") (pintype "passive"))
      (node (ref "R1042") (pin "2") (pinfunction "2_2") (pintype "passive"))
    )
    (net (code "111") (name "Net-(CN1001-Pad66)") (class "Default")
      (node (ref "CN1001") (pin "66") (pinfunction "66_66") (pintype "passive"))
      (node (ref "R1043") (pin "1") (pinfunction "1_1") (pintype "passive"))
    )
    (net (code "112") (name "Net-(CN1001-Pad69)") (class "Default")
      (node (ref "CN1001") (pin "69") (pinfunction "69_69") (pintype "passive"))
      (node (ref "R1045") (pin "2") (pinfunction "2_2") (pintype "passive"))
    )
    (net (code "113") (name "Net-(CN1001-Pad70)") (class "Default")
      (node (ref "CN1001") (pin "70") (pinfunction "70_70") (pintype "passive"))
      (node (ref "R1046") (pin "1") (pinfunction "1_1") (pintype "passive"))
    )
    (net (code "114") (name "Net-(CN1001-Pad73)") (class "Default")
      (node (ref "CN1001") (pin "73") (pinfunction "73_73") (pintype "passive"))
      (node (ref "R1048") (pin "2") (pinfunction "2_2") (pintype "passive"))
    )
    (net (code "115") (name "Net-(CN1001-Pad74)") (class "Default")
      (node (ref "CN1001") (pin "74") (pinfunction "74_74") (pintype "passive"))
      (node (ref "R1049") (pin "1") (pinfunction "1_1") (pintype "passive"))
    )
    (net (code "116") (name "Net-(CN1001-Pad78)") (class "Default")
      (node (ref "CN1001") (pin "78") (pinfunction "78_78") (pintype "passive"))
      (node (ref "R1051") (pin "1") (pinfunction "1_1") (pintype "passive"))
    )
    (net (code "117") (name "Net-(CN1001-Pad82)") (class "Default")
      (node (ref "CN1001") (pin "82") (pinfunction "82_82") (pintype "passive"))
      (node (ref "R1053") (pin "1") (pinfunction "1_1") (pintype "passive"))
    )
    (net (code "118") (name "Net-(CN1001-Pad86)") (class "Default")
      (node (ref "CN1001") (pin "86") (pinfunction "86_86") (pintype "passive"))
      (node (ref "R1054") (pin "1") (pinfunction "1_1") (pintype "passive"))
    )
    (net (code "119") (name "Net-(CN1001-Pad90)") (class "Default")
      (node (ref "CN1001") (pin "90") (pinfunction "90_90") (pintype "passive"))
      (node (ref "R1055") (pin "1") (pinfunction "1_1") (pintype "passive"))
    )
    (net (code "120") (name "unconnected-(CN1000-Pad46)") (class "Default")
      (node (ref "CN1000") (pin "46") (pinfunction "46_46") (pintype "passive"))
    )
    (net (code "121") (name "unconnected-(CN1000-Pad50)") (class "Default")
      (node (ref "CN1000") (pin "50") (pinfunction "50_50") (pintype "passive"))
    )
    (net (code "122") (name "unconnected-(CN1000-Pad54)") (class "Default")
      (node (ref "CN1000") (pin "54") (pinfunction "54_54") (pintype "passive"))
    )
    (net (code "123") (name "unconnected-(CN1000-Pad58)") (class "Default")
      (node (ref "CN1000") (pin "58") (pinfunction "58_58") (pintype "passive"))
    )
    (net (code "124") (name "unconnected-(CN1000-Pad62)") (class "Default")
      (node (ref "CN1000") (pin "62") (pinfunction "62_62") (pintype "passive"))
    )
    (net (code "125") (name "unconnected-(CN1000-Pad66)") (class "Default")
      (node (ref "CN1000") (pin "66") (pinfunction "66_66") (pintype "passive"))
    )
    (net (code "126") (name "unconnected-(CN1000-Pad70)") (class "Default")
      (node (ref "CN1000") (pin "70") (pinfunction "70_70") (pintype "passive"))
    )
    (net (code "127") (name "unconnected-(CN1000-Pad74)") (class "Default")
      (node (ref "CN1000") (pin "74") (pinfunction "74_74") (pintype "passive"))
    )
    (net (code "128") (name "unconnected-(CN1000-Pad78)") (class "Default")
      (node (ref "CN1000") (pin "78") (pinfunction "78_78") (pintype "passive"))
    )
    (net (code "129") (name "unconnected-(CN1000-Pad82)") (class "Default")
      (node (ref "CN1000") (pin "82") (pinfunction "82_82") (pintype "passive"))
    )
    (net (code "130") (name "unconnected-(CN1000-Pad86)") (class "Default")
      (node (ref "CN1000") (pin "86") (pinfunction "86_86") (pintype "passive"))
    )
    (net (code "131") (name "unconnected-(CN1000-Pad90)") (class "Default")
      (node (ref "CN1000") (pin "90") (pinfunction "90_90") (pintype "passive"))
    )
    (net (code "132") (name "unconnected-(CN1000-Pad94)") (class "Default")
      (node (ref "CN1000") (pin "94") (pinfunction "94_94") (pintype "passive"))
    )
    (net (code "133") (name "unconnected-(CN1000-Pad98)") (class "Default")
      (node (ref "CN1000") (pin "98") (pinfunction "98_98") (pintype "passive"))
    )
    (net (code "134") (name "unconnected-(CN1001-Pad9)") (class "Default")
      (node (ref "CN1001") (pin "9") (pinfunction "9_9") (pintype "passive+no_connect"))
    )
    (net (code "135") (name "unconnected-(CN1001-Pad10)") (class "Default")
      (node (ref "CN1001") (pin "10") (pinfunction "10_10") (pintype "passive+no_connect"))
    )
    (net (code "136") (name "unconnected-(CN1001-Pad11)") (class "Default")
      (node (ref "CN1001") (pin "11") (pinfunction "11_11") (pintype "passive+no_connect"))
    )
    (net (code "137") (name "unconnected-(CN1001-Pad12)") (class "Default")
      (node (ref "CN1001") (pin "12") (pinfunction "12_12") (pintype "passive+no_connect"))
    )
    (net (code "138") (name "unconnected-(CN1001-Pad21)") (class "Default")
      (node (ref "CN1001") (pin "21") (pinfunction "21_21") (pintype "passive+no_connect"))
    )
    (net (code "139") (name "unconnected-(CN1001-Pad22)") (class "Default")
      (node (ref "CN1001") (pin "22") (pinfunction "22_22") (pintype "passive+no_connect"))
    )
    (net (code "140") (name "unconnected-(CN1001-Pad23)") (class "Default")
      (node (ref "CN1001") (pin "23") (pinfunction "23_23") (pintype "passive+no_connect"))
    )
    (net (code "141") (name "unconnected-(CN1001-Pad24)") (class "Default")
      (node (ref "CN1001") (pin "24") (pinfunction "24_24") (pintype "passive+no_connect"))
    )
    (net (code "142") (name "unconnected-(CN1001-Pad31)") (class "Default")
      (node (ref "CN1001") (pin "31") (pinfunction "31_31") (pintype "passive+no_connect"))
    )
    (net (code "143") (name "unconnected-(CN1001-Pad32)") (class "Default")
      (node (ref "CN1001") (pin "32") (pinfunction "32_32") (pintype "passive+no_connect"))
    )
    (net (code "144") (name "unconnected-(CN1001-Pad33)") (class "Default")
      (node (ref "CN1001") (pin "33") (pinfunction "33_33") (pintype "passive+no_connect"))
    )
    (net (code "145") (name "unconnected-(CN1001-Pad34)") (class "Default")
      (node (ref "CN1001") (pin "34") (pinfunction "34_34") (pintype "passive+no_connect"))
    )
    (net (code "146") (name "unconnected-(CN1001-Pad41)") (class "Default")
      (node (ref "CN1001") (pin "41") (pinfunction "41_41") (pintype "passive+no_connect"))
    )
    (net (code "147") (name "unconnected-(CN1001-Pad42)") (class "Default")
      (node (ref "CN1001") (pin "42") (pinfunction "42_42") (pintype "passive+no_connect"))
    )
    (net (code "148") (name "unconnected-(CN1001-Pad43)") (class "Default")
      (node (ref "CN1001") (pin "43") (pinfunction "43_43") (pintype "passive+no_connect"))
    )
    (net (code "149") (name "unconnected-(CN1001-Pad44)") (class "Default")
      (node (ref "CN1001") (pin "44") (pinfunction "44_44") (pintype "passive+no_connect"))
    )
    (net (code "150") (name "unconnected-(CN1001-Pad77)") (class "Default")
      (node (ref "CN1001") (pin "77") (pinfunction "77_77") (pintype "passive"))
    )
    (net (code "151") (name "unconnected-(CN1001-Pad81)") (class "Default")
      (node (ref "CN1001") (pin "81") (pinfunction "81_81") (pintype "passive"))
    )
    (net (code "152") (name "unconnected-(CN1001-Pad85)") (class "Default")
      (node (ref "CN1001") (pin "85") (pinfunction "85_85") (pintype "passive"))
    )
    (net (code "153") (name "unconnected-(CN1001-Pad89)") (class "Default")
      (node (ref "CN1001") (pin "89") (pinfunction "89_89") (pintype "passive"))
    )
    (net (code "154") (name "unconnected-(CN1001-Pad93)") (class "Default")
      (node (ref "CN1001") (pin "93") (pinfunction "93_93") (pintype "passive"))
    )
    (net (code "155") (name "unconnected-(CN1001-Pad94)") (class "Default")
      (node (ref "CN1001") (pin "94") (pinfunction "94_94") (pintype "passive"))
    )
    (net (code "156") (name "unconnected-(CN1001-Pad97)") (class "Default")
      (node (ref "CN1001") (pin "97") (pinfunction "97_97") (pintype "passive"))
    )
    (net (code "157") (name "unconnected-(CN1001-Pad98)") (class "Default")
      (node (ref "CN1001") (pin "98") (pinfunction "98_98") (pintype "passive"))
    )
    (net (code "158") (name "unconnected-(H1000-Pad1)") (class "Default")
      (node (ref "H1000") (pin "1") (pinfunction "1_1") (pintype "passive+no_connect"))
    )
    (net (code "159") (name "unconnected-(H1001-Pad1)") (class "Default")
      (node (ref "H1001") (pin "1") (pinfunction "1_1") (pintype "passive+no_connect"))
    )
    (net (code "160") (name "unconnected-(H1002-Pad1)") (class "Default")
      (node (ref "H1002") (pin "1") (pinfunction "1_1") (pintype "passive+no_connect"))
    )
    (net (code "161") (name "unconnected-(H1003-Pad1)") (class "Default")
      (node (ref "H1003") (pin "1") (pinfunction "1_1") (pintype "passive+no_connect"))
    )
  )
)
